# MCU.net
KiCad netlist of a schematic drawn in Altium Designer
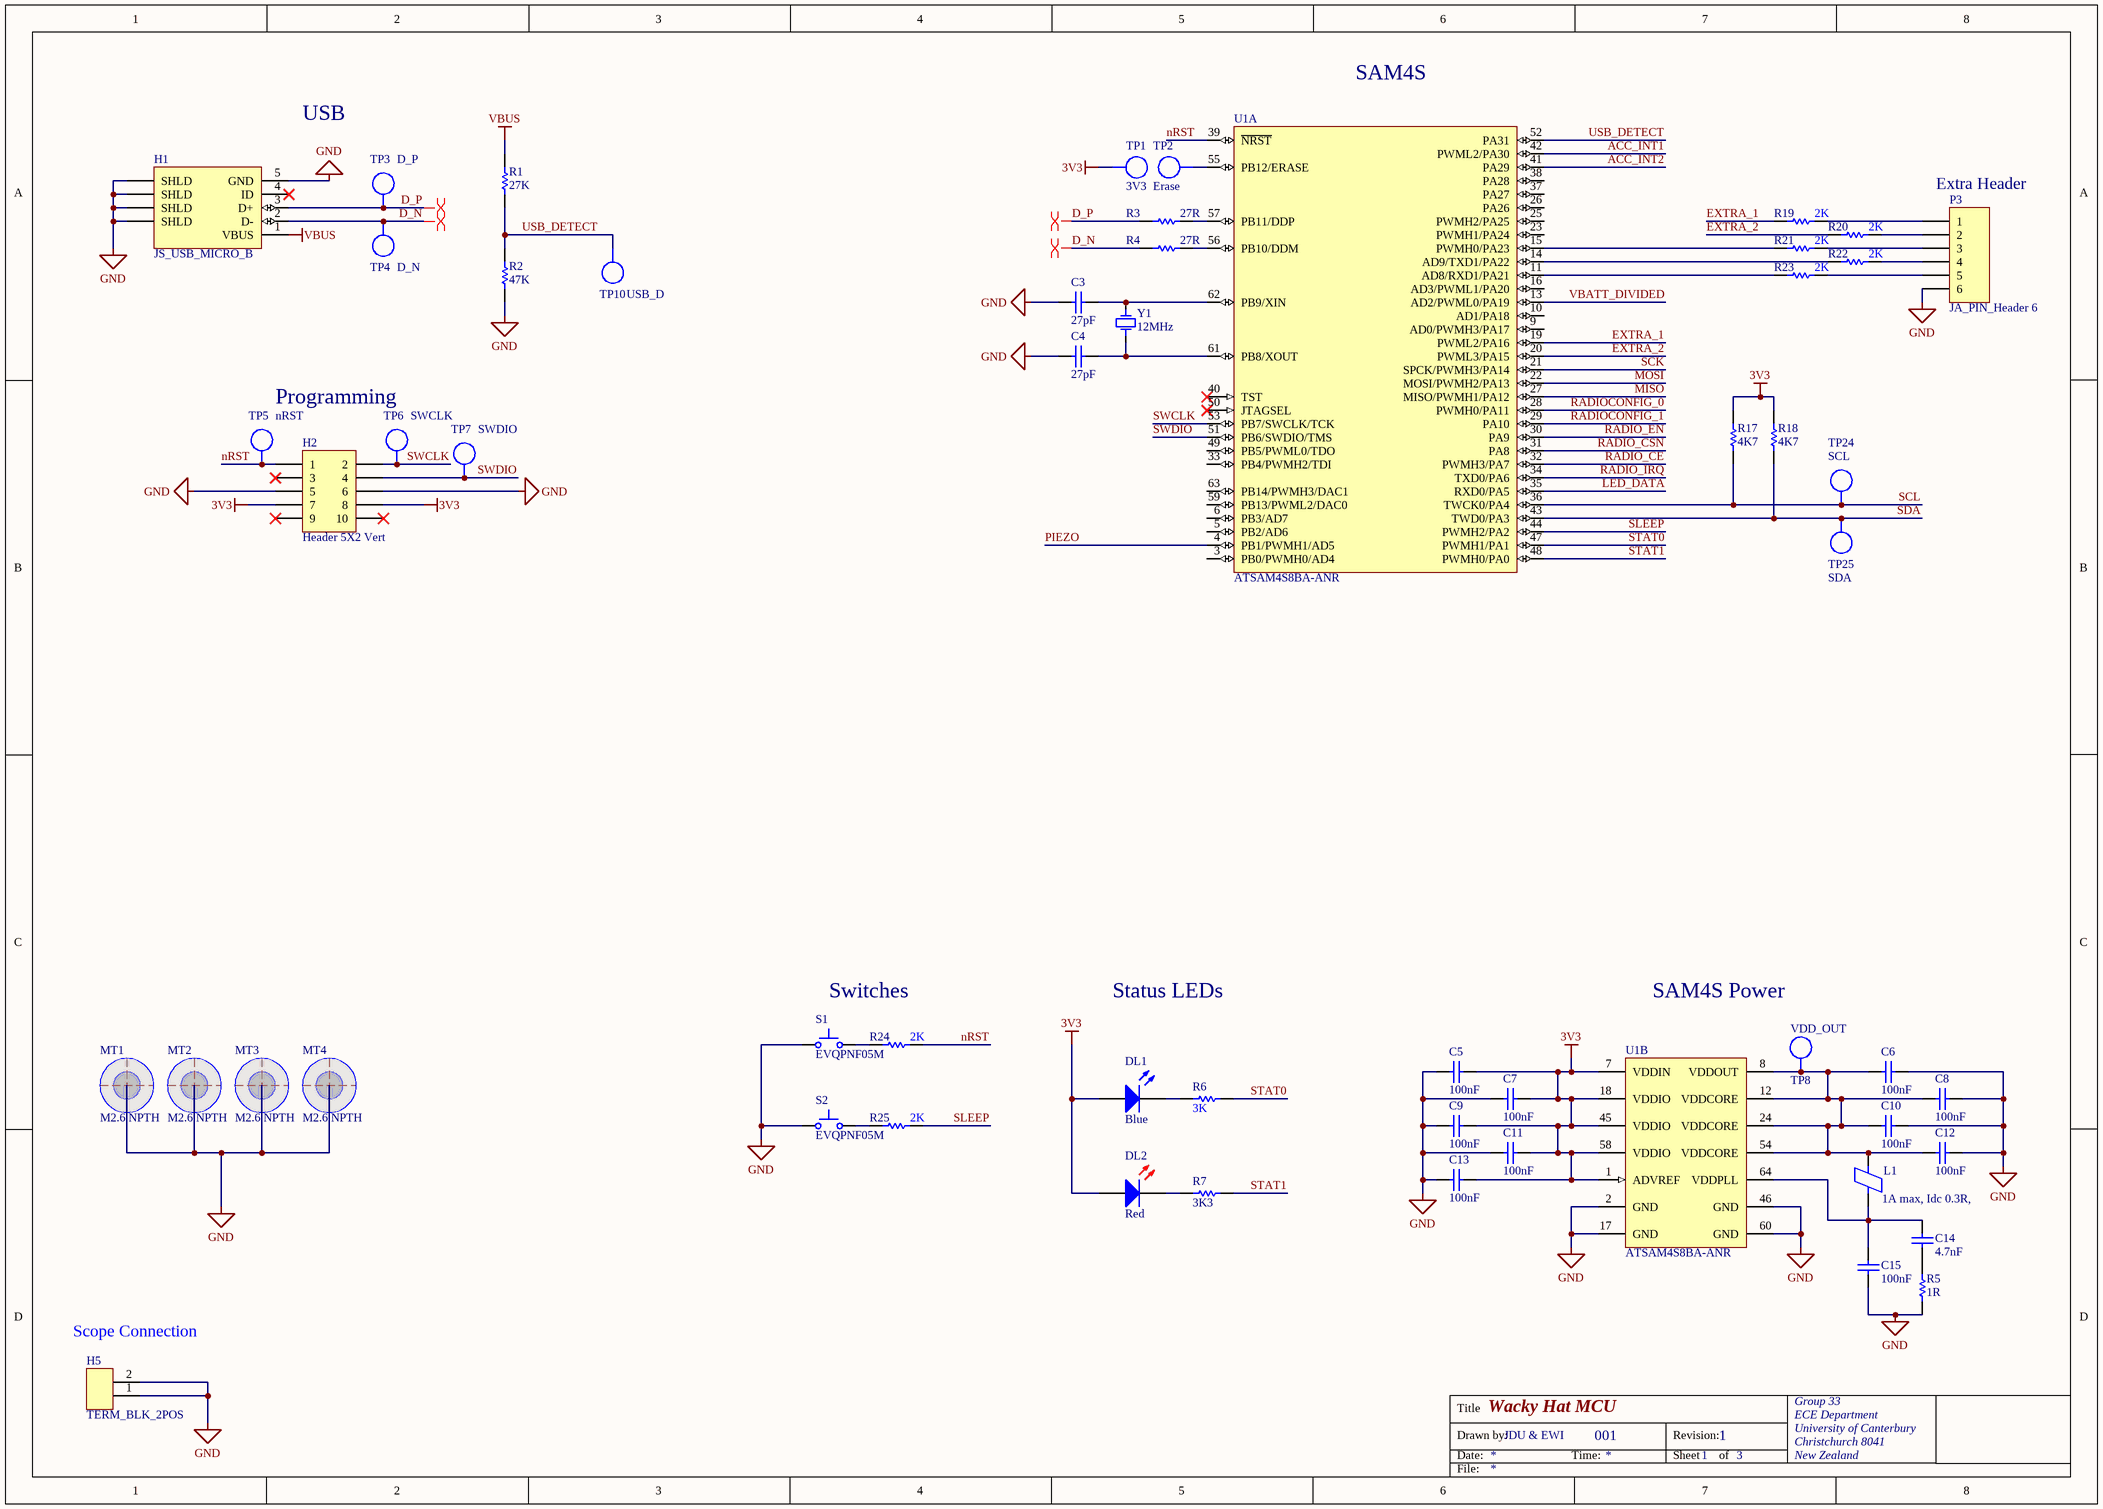
[diagram p0: MCU.SchDoc]

(export (version "E")
  (design (tool "Eeschema 10.0.6"))
  (components
    (comp (ref "C3")
      (value "27pF")
      (footprint "CAPC1608L")
      (description "CAP CER 27pF NPO/COG +-5% 50V 0603")
      (libsource (lib "ECE_ComponentsAD23") (part "CC_27pF_0603"))
    )
    (comp (ref "C4")
      (value "27pF")
      (footprint "CAPC1608L")
      (description "CAP CER 27pF NPO/COG +-5% 50V 0603")
      (libsource (lib "ECE_ComponentsAD23") (part "CC_27pF_0603"))
    )
    (comp (ref "C5")
      (value "100nF")
      (footprint "CAPC1608L")
      (description "CAP CER 100nF X7R +-10% 50V 0603")
      (libsource (lib "ECE_ComponentsAD23") (part "CC_100nF_0603"))
    )
    (comp (ref "C6")
      (value "100nF")
      (footprint "CAPC1608L")
      (description "CAP CER 100nF X7R +-10% 50V 0603")
      (libsource (lib "ECE_ComponentsAD23") (part "CC_100nF_0603"))
    )
    (comp (ref "C7")
      (value "100nF")
      (footprint "CAPC1608L")
      (description "CAP CER 100nF X7R +-10% 50V 0603")
      (libsource (lib "ECE_ComponentsAD23") (part "CC_100nF_0603"))
    )
    (comp (ref "C8")
      (value "100nF")
      (footprint "CAPC1608L")
      (description "CAP CER 100nF X7R +-10% 50V 0603")
      (libsource (lib "ECE_ComponentsAD23") (part "CC_100nF_0603"))
    )
    (comp (ref "C9")
      (value "100nF")
      (footprint "CAPC1608L")
      (description "CAP CER 100nF X7R +-10% 50V 0603")
      (libsource (lib "ECE_ComponentsAD23") (part "CC_100nF_0603"))
    )
    (comp (ref "C10")
      (value "100nF")
      (footprint "CAPC1608L")
      (description "CAP CER 100nF X7R +-10% 50V 0603")
      (libsource (lib "ECE_ComponentsAD23") (part "CC_100nF_0603"))
    )
    (comp (ref "C11")
      (value "100nF")
      (footprint "CAPC1608L")
      (description "CAP CER 100nF X7R +-10% 50V 0603")
      (libsource (lib "ECE_ComponentsAD23") (part "CC_100nF_0603"))
    )
    (comp (ref "C12")
      (value "100nF")
      (footprint "CAPC1608L")
      (description "CAP CER 100nF X7R +-10% 50V 0603")
      (libsource (lib "ECE_ComponentsAD23") (part "CC_100nF_0603"))
    )
    (comp (ref "C13")
      (value "100nF")
      (footprint "CAPC1608L")
      (description "CAP CER 100nF X7R +-10% 50V 0603")
      (libsource (lib "ECE_ComponentsAD23") (part "CC_100nF_0603"))
    )
    (comp (ref "C14")
      (value "4.7nF")
      (footprint "CAPC1608L")
      (description "CAP CER 4.7nF X7R +-10% 50V 0603")
      (libsource (lib "ECE_ComponentsAD23") (part "CC_4.7nF_0603"))
    )
    (comp (ref "C15")
      (value "100nF")
      (footprint "CAPC1608L")
      (description "CAP CER 100nF X7R +-10% 50V 0603")
      (libsource (lib "ECE_ComponentsAD23") (part "CC_100nF_0603"))
    )
    (comp (ref "DL1")
      (value "Blue")
      (footprint "WL-SMCW0603")
      (description "LED Blue 270mcd 0603 SMD")
      (fields
        (field (name "MANUFACTURER") "WURTH ELEKTRONIK")
        (field (name "MANUFACTURER PART NUMBER") "150060BS75000")
        (field (name "LED COLOUR") "Blue")
      )
      (libsource (lib "ECE_ComponentsAD23") (part "DL_150060BS75000"))
    )
    (comp (ref "DL2")
      (value "Red")
      (footprint "WL-SMCW0603")
      (description "LED Red 250mcd 0603 SMD")
      (fields
        (field (name "MANUFACTURER") "WURTH ELEKTRONIK")
        (field (name "MANUFACTURER PART NUMBER") "150060RS75000")
        (field (name "LED COLOUR") "Red")
      )
      (libsource (lib "ECE_ComponentsAD23") (part "DL_150060RS75000"))
    )
    (comp (ref "H1")
      (value "JS_USB_MICRO_B")
      (footprint "FCI_USB_10118194-0001LF")
      (description "CONN USB MICRO B RECPT SMT R/A")
      (fields (field (name "MANUFACTURER") "FCI") (field (name "MANUFACTURER PART NUMBER") "10118194-0001LF"))
      (libsource (lib "ECE_ComponentsAD23") (part "JS_USB_MICRO_B_SMT"))
    )
    (comp (ref "H2")
      (value "Header 5X2 Vert")
      (footprint "IDC2.54-V10D")
      (description "IDC Header, 2,54mm, 10-Pin, Vert")
      (libsource (lib "ECE_ComponentsAD23") (part "JA_HDR_IDC_5X2_VERT"))
    )
    (comp (ref "H5")
      (value "TERM_BLK_2POS")
      (footprint "TERM_BLK_2POS")
      (description "2 Position Terminal Block 7.62mm spacing")
      (libsource (lib "ENCE461AD23") (part "TERM_BLK_2POS"))
    )
    (comp (ref "L1")
      (value "1A max, Idc 0.3R,")
      (footprint "INDC3216L")
      (description "Ferrite Bead, Rdc 0.3R, Z100MHZ 600R, Imax 1A, SMD 1206")
      (fields
        (field (name "MANUFACTURER") "FAIR-RITE")
        (field (name "MANUFACTURER PART NUMBER") "2512066017Y1")
      )
      (libsource (lib "ECE_ComponentsAD23") (part "IN_Ferrite-Bead"))
    )
    (comp (ref "MT1")
      (value "M2.6 NPTH")
      (footprint "MNT-HOLE_2.6mm_NPTH")
      (description "Fixing M2.6 Mount Hole NPTH")
      (fields (field (name "MANUFACTURER") "Hi-Q"))
      (libsource (lib "ECE_ComponentsAD23") (part "MC_M2.6_HOLE"))
    )
    (comp (ref "MT2")
      (value "M2.6 NPTH")
      (footprint "MNT-HOLE_2.6mm_NPTH")
      (description "Fixing M2.6 Mount Hole NPTH")
      (fields (field (name "MANUFACTURER") "Hi-Q"))
      (libsource (lib "ECE_ComponentsAD23") (part "MC_M2.6_HOLE"))
    )
    (comp (ref "MT3")
      (value "M2.6 NPTH")
      (footprint "MNT-HOLE_2.6mm_NPTH")
      (description "Fixing M2.6 Mount Hole NPTH")
      (fields (field (name "MANUFACTURER") "Hi-Q"))
      (libsource (lib "ECE_ComponentsAD23") (part "MC_M2.6_HOLE"))
    )
    (comp (ref "MT4")
      (value "M2.6 NPTH")
      (footprint "MNT-HOLE_2.6mm_NPTH")
      (description "Fixing M2.6 Mount Hole NPTH")
      (fields (field (name "MANUFACTURER") "Hi-Q"))
      (libsource (lib "ECE_ComponentsAD23") (part "MC_M2.6_HOLE"))
    )
    (comp (ref "P3")
      (value "JA_PIN_Header 6")
      (footprint "HDR1X6")
      (description "Header, 6-Pin")
      (fields (field (name "PUBLISHER") "Altium Limited"))
      (libsource (lib "ECE_ComponentsAD23") (part "JA_PIN_Header 6"))
    )
    (comp (ref "R1")
      (value "27K")
      (footprint "RESC1608L")
      (description "RES 27K OHM 1/10W 5% 0603 SMD")
      (libsource (lib "ECE_ComponentsAD23") (part "RS_27K"))
    )
    (comp (ref "R2")
      (value "47K")
      (footprint "RESC1608N")
      (description "RES 47.0K OHM 1/10W 5% 0603 SMD")
      (libsource (lib "ECE_ComponentsAD23") (part "RS_47K"))
    )
    (comp (ref "R3")
      (value "27R")
      (footprint "RESC1608L")
      (description "RES 27 OHM 1/10W 5% 0603 SMD")
      (libsource (lib "ECE_ComponentsAD23") (part "RS_27R"))
    )
    (comp (ref "R4")
      (value "27R")
      (footprint "RESC1608L")
      (description "RES 27 OHM 1/10W 5% 0603 SMD")
      (libsource (lib "ECE_ComponentsAD23") (part "RS_27R"))
    )
    (comp (ref "R5")
      (value "1R")
      (footprint "RESC3216L")
      (description "RES 1R OHM 1/4W 5% 1206 SMD")
      (libsource (lib "ECE_ComponentsAD23") (part "RT_1R"))
    )
    (comp (ref "R6")
      (value "3K")
      (footprint "RESC1608L")
      (description "RES 3K OHM 1/10W 5% 0603 SMD")
      (libsource (lib "ECE_ComponentsAD23") (part "RS_3K"))
    )
    (comp (ref "R7")
      (value "3K3")
      (footprint "RESC1608L")
      (description "RES 1.5K OHM 1/10W 5% 0603 SMD")
      (libsource (lib "ECE_ComponentsAD23") (part "RS_1K5"))
    )
    (comp (ref "R17")
      (value "4K7")
      (footprint "RESC1608L")
      (description "RES 4.7K OHM 1/10W 5% 0603 SMD")
      (libsource (lib "ECE_ComponentsAD23") (part "RS_4K7"))
    )
    (comp (ref "R18")
      (value "4K7")
      (footprint "RESC1608L")
      (description "RES 4.7K OHM 1/10W 5% 0603 SMD")
      (libsource (lib "ECE_ComponentsAD23") (part "RS_4K7"))
    )
    (comp (ref "R19")
      (value "2K")
      (footprint "RESC1608L")
      (description "RES 2K OHM 1/10W 5% 0603 SMD")
      (libsource (lib "ECE_ComponentsAD23") (part "RS_2K"))
    )
    (comp (ref "R20")
      (value "2K")
      (footprint "RESC1608L")
      (description "RES 2K OHM 1/10W 5% 0603 SMD")
      (libsource (lib "ECE_ComponentsAD23") (part "RS_2K"))
    )
    (comp (ref "R21")
      (value "2K")
      (footprint "RESC1608L")
      (description "RES 2K OHM 1/10W 5% 0603 SMD")
      (libsource (lib "ECE_ComponentsAD23") (part "RS_2K"))
    )
    (comp (ref "R22")
      (value "2K")
      (footprint "RESC1608L")
      (description "RES 2K OHM 1/10W 5% 0603 SMD")
      (libsource (lib "ECE_ComponentsAD23") (part "RS_2K"))
    )
    (comp (ref "R23")
      (value "2K")
      (footprint "RESC1608L")
      (description "RES 2K OHM 1/10W 5% 0603 SMD")
      (libsource (lib "ECE_ComponentsAD23") (part "RS_2K"))
    )
    (comp (ref "R24")
      (value "2K")
      (footprint "RESC1608L")
      (description "RES 2K OHM 1/10W 5% 0603 SMD")
      (libsource (lib "ECE_ComponentsAD23") (part "RS_2K"))
    )
    (comp (ref "R25")
      (value "2K")
      (footprint "RESC1608L")
      (description "RES 2K OHM 1/10W 5% 0603 SMD")
      (libsource (lib "ECE_ComponentsAD23") (part "RS_2K"))
    )
    (comp (ref "S1")
      (value "EVQPNF05M")
      (footprint "EVQPNF05M")
      (description "Panasonic 6 x 3.5mm SMD Light Touch Switch Type SMD")
      (fields (field (name "MANUFACTURER") "Panasonic"))
      (libsource (lib "ECE_ComponentsAD23") (part "WS_EVQPNF05M"))
    )
    (comp (ref "S2")
      (value "EVQPNF05M")
      (footprint "EVQPNF05M")
      (description "Panasonic 6 x 3.5mm SMD Light Touch Switch Type SMD")
      (fields (field (name "MANUFACTURER") "Panasonic"))
      (libsource (lib "ECE_ComponentsAD23") (part "WS_EVQPNF05M"))
    )
    (comp (ref "TP1")
      (value "3V3")
      (footprint "TP_1206")
      (description "Test-Point 3.3x1.6x2.1mm SMD")
      (fields
        (field (name "MANUFACTURER") "Harwin Inc")
        (field (name "MANUFACTURER PART NUMBER") "S1751-46R")
      )
      (libsource (lib "ECE_ComponentsAD23") (part "TP_1206"))
    )
    (comp (ref "TP2")
      (value "Erase")
      (footprint "TP_1206")
      (description "Test-Point 3.3x1.6x2.1mm SMD")
      (fields
        (field (name "MANUFACTURER") "Harwin Inc")
        (field (name "MANUFACTURER PART NUMBER") "S1751-46R")
      )
      (libsource (lib "ECE_ComponentsAD23") (part "TP_1206"))
    )
    (comp (ref "TP3")
      (value "D_P")
      (footprint "TP_1206")
      (description "Test-Point 3.3x1.6x2.1mm SMD")
      (fields
        (field (name "MANUFACTURER") "Harwin Inc")
        (field (name "MANUFACTURER PART NUMBER") "S1751-46R")
      )
      (libsource (lib "ECE_ComponentsAD23") (part "TP_1206"))
    )
    (comp (ref "TP4")
      (value "D_N")
      (footprint "TP_1206")
      (description "Test-Point 3.3x1.6x2.1mm SMD")
      (fields
        (field (name "MANUFACTURER") "Harwin Inc")
        (field (name "MANUFACTURER PART NUMBER") "S1751-46R")
      )
      (libsource (lib "ECE_ComponentsAD23") (part "TP_1206"))
    )
    (comp (ref "TP5")
      (value "nRST")
      (footprint "TP_1206")
      (description "Test-Point 3.3x1.6x2.1mm SMD")
      (fields
        (field (name "MANUFACTURER") "Harwin Inc")
        (field (name "MANUFACTURER PART NUMBER") "S1751-46R")
      )
      (libsource (lib "ECE_ComponentsAD23") (part "TP_1206"))
    )
    (comp (ref "TP6")
      (value "SWCLK")
      (footprint "TP_1206")
      (description "Test-Point 3.3x1.6x2.1mm SMD")
      (fields
        (field (name "MANUFACTURER") "Harwin Inc")
        (field (name "MANUFACTURER PART NUMBER") "S1751-46R")
      )
      (libsource (lib "ECE_ComponentsAD23") (part "TP_1206"))
    )
    (comp (ref "TP7")
      (value "SWDIO")
      (footprint "TP_1206")
      (description "Test-Point 3.3x1.6x2.1mm SMD")
      (fields
        (field (name "MANUFACTURER") "Harwin Inc")
        (field (name "MANUFACTURER PART NUMBER") "S1751-46R")
      )
      (libsource (lib "ECE_ComponentsAD23") (part "TP_1206"))
    )
    (comp (ref "TP8")
      (value "VDD_OUT")
      (footprint "TP_1206")
      (description "Test-Point 3.3x1.6x2.1mm SMD")
      (fields
        (field (name "MANUFACTURER") "Harwin Inc")
        (field (name "MANUFACTURER PART NUMBER") "S1751-46R")
      )
      (libsource (lib "ECE_ComponentsAD23") (part "TP_1206"))
    )
    (comp (ref "TP10")
      (value "USB_D")
      (footprint "TP_1206")
      (description "Test-Point 3.3x1.6x2.1mm SMD")
      (fields
        (field (name "MANUFACTURER") "Harwin Inc")
        (field (name "MANUFACTURER PART NUMBER") "S1751-46R")
      )
      (libsource (lib "ECE_ComponentsAD23") (part "TP_1206"))
    )
    (comp (ref "TP24")
      (value "SCL")
      (footprint "TP_1206")
      (description "Test-Point 3.3x1.6x2.1mm SMD")
      (fields
        (field (name "MANUFACTURER") "Harwin Inc")
        (field (name "MANUFACTURER PART NUMBER") "S1751-46R")
      )
      (libsource (lib "ECE_ComponentsAD23") (part "TP_1206"))
    )
    (comp (ref "TP25")
      (value "SDA")
      (footprint "TP_1206")
      (description "Test-Point 3.3x1.6x2.1mm SMD")
      (fields
        (field (name "MANUFACTURER") "Harwin Inc")
        (field (name "MANUFACTURER PART NUMBER") "S1751-46R")
      )
      (libsource (lib "ECE_ComponentsAD23") (part "TP_1206"))
    )
    (comp (ref "U1")
      (value "ATSAM4S8BA-ANR")
      (footprint "LQFP64_L")
      (description "IC MCU 32BIT 512KB FLASH 64LQFP")
      (fields (field (name "MANUFACTURER") "Atmel"))
      (libsource (lib "ECE_ComponentsAD23") (part "SE_ATSAM4S16BA-MU"))
    )
    (comp (ref "Y1")
      (value "12MHz")
      (footprint "6.0X3.5-4")
      (description "CRYSTAL 12MHZ 18PF 6X3.5mm SMD")
      (fields
        (field (name "MANUFACTURER") "CTS-Frequency Controls")
        (field (name "MANUFACTURER PART NUMBER") "406C35D12M00000")
        (field (name "FREQUENCY") "12MHz")
      )
      (libsource (lib "ECE_ComponentsAD23") (part "XT_CRYSTAL_12MHz_18pF"))
    )
  )
  (nets
    (net (code "1") (name "/ACC_INT1") (class "Default")
      (node (ref "U1") (pin "42") (pinfunction "PWML2/PA30_42") (pintype "bidirectional"))
    )
    (net (code "2") (name "/ACC_INT2") (class "Default")
      (node (ref "U1") (pin "41") (pinfunction "PA29_41") (pintype "bidirectional"))
    )
    (net (code "3") (name "/D_N") (class "Default")
      (node (ref "H1") (pin "2") (pinfunction "D-_2") (pintype "bidirectional"))
      (node (ref "R4") (pin "1") (pinfunction "1_1") (pintype "passive"))
      (node (ref "TP4") (pin "1") (pinfunction "1_1") (pintype "passive"))
    )
    (net (code "4") (name "/D_P") (class "Default")
      (node (ref "H1") (pin "3") (pinfunction "D+_3") (pintype "bidirectional"))
      (node (ref "R3") (pin "1") (pinfunction "1_1") (pintype "passive"))
      (node (ref "TP3") (pin "1") (pinfunction "1_1") (pintype "passive"))
    )
    (net (code "5") (name "/EXTRA_1") (class "Default")
      (node (ref "R19") (pin "1") (pinfunction "1_1") (pintype "passive"))
      (node (ref "U1") (pin "19") (pinfunction "PWML2/PA16_19") (pintype "bidirectional"))
    )
    (net (code "6") (name "/EXTRA_2") (class "Default")
      (node (ref "R20") (pin "1") (pinfunction "1_1") (pintype "passive"))
      (node (ref "U1") (pin "20") (pinfunction "PWML3/PA15_20") (pintype "bidirectional"))
    )
    (net (code "7") (name "/LED_DATA") (class "Default")
      (node (ref "U1") (pin "35") (pinfunction "RXD0/PA5_35") (pintype "bidirectional"))
    )
    (net (code "8") (name "/MISO") (class "Default")
      (node (ref "U1") (pin "27") (pinfunction "MISO/PWMH1/PA12_27") (pintype "bidirectional"))
    )
    (net (code "9") (name "/MOSI") (class "Default")
      (node (ref "U1") (pin "22") (pinfunction "MOSI/PWMH2/PA13_22") (pintype "bidirectional"))
    )
    (net (code "10") (name "/PIEZO") (class "Default")
      (node (ref "U1") (pin "4") (pinfunction "PB1/PWMH1/AD5_4") (pintype "bidirectional"))
    )
    (net (code "11") (name "/RADIOCONFIG_0") (class "Default")
      (node (ref "U1") (pin "28") (pinfunction "PWMH0/PA11_28") (pintype "bidirectional"))
    )
    (net (code "12") (name "/RADIOCONFIG_1") (class "Default")
      (node (ref "U1") (pin "29") (pinfunction "PA10_29") (pintype "bidirectional"))
    )
    (net (code "13") (name "/RADIO_CE") (class "Default")
      (node (ref "U1") (pin "32") (pinfunction "PWMH3/PA7_32") (pintype "bidirectional"))
    )
    (net (code "14") (name "/RADIO_CSN") (class "Default")
      (node (ref "U1") (pin "31") (pinfunction "PA8_31") (pintype "bidirectional"))
    )
    (net (code "15") (name "/RADIO_EN") (class "Default")
      (node (ref "U1") (pin "30") (pinfunction "PA9_30") (pintype "bidirectional"))
    )
    (net (code "16") (name "/RADIO_IRQ") (class "Default")
      (node (ref "U1") (pin "34") (pinfunction "TXD0/PA6_34") (pintype "bidirectional"))
    )
    (net (code "17") (name "/SCK") (class "Default")
      (node (ref "U1") (pin "21") (pinfunction "SPCK/PWMH3/PA14_21") (pintype "bidirectional"))
    )
    (net (code "18") (name "/SCL") (class "Default")
      (node (ref "R17") (pin "1") (pinfunction "1_1") (pintype "passive"))
      (node (ref "TP24") (pin "1") (pinfunction "1_1") (pintype "passive"))
      (node (ref "U1") (pin "36") (pinfunction "TWCK0/PA4_36") (pintype "bidirectional"))
    )
    (net (code "19") (name "/SDA") (class "Default")
      (node (ref "R18") (pin "1") (pinfunction "1_1") (pintype "passive"))
      (node (ref "TP25") (pin "1") (pinfunction "1_1") (pintype "passive"))
      (node (ref "U1") (pin "43") (pinfunction "TWD0/PA3_43") (pintype "bidirectional"))
    )
    (net (code "20") (name "/SLEEP") (class "Default")
      (node (ref "R25") (pin "2") (pinfunction "2_2") (pintype "passive"))
      (node (ref "U1") (pin "44") (pinfunction "PWMH2/PA2_44") (pintype "bidirectional"))
    )
    (net (code "21") (name "/STAT0") (class "Default")
      (node (ref "R6") (pin "2") (pinfunction "2_2") (pintype "passive"))
      (node (ref "U1") (pin "47") (pinfunction "PWMH1/PA1_47") (pintype "bidirectional"))
    )
    (net (code "22") (name "/STAT1") (class "Default")
      (node (ref "R7") (pin "2") (pinfunction "2_2") (pintype "passive"))
      (node (ref "U1") (pin "48") (pinfunction "PWMH0/PA0_48") (pintype "bidirectional"))
    )
    (net (code "23") (name "/SWCLK") (class "Default")
      (node (ref "H2") (pin "2") (pinfunction "2_2") (pintype "passive"))
      (node (ref "TP6") (pin "1") (pinfunction "1_1") (pintype "passive"))
      (node (ref "U1") (pin "53") (pinfunction "PB7/SWCLK/TCK_53") (pintype "bidirectional"))
    )
    (net (code "24") (name "/SWDIO") (class "Default")
      (node (ref "H2") (pin "4") (pinfunction "4_4") (pintype "passive"))
      (node (ref "TP7") (pin "1") (pinfunction "1_1") (pintype "passive"))
      (node (ref "U1") (pin "51") (pinfunction "PB6/SWDIO/TMS_51") (pintype "bidirectional"))
    )
    (net (code "25") (name "/USB_DETECT") (class "Default")
      (node (ref "R1") (pin "1") (pinfunction "1_1") (pintype "passive"))
      (node (ref "R2") (pin "2") (pinfunction "2_2") (pintype "passive"))
      (node (ref "TP10") (pin "1") (pinfunction "1_1") (pintype "passive"))
      (node (ref "U1") (pin "52") (pinfunction "PA31_52") (pintype "bidirectional"))
    )
    (net (code "26") (name "/VBATT_DIVIDED") (class "Default")
      (node (ref "U1") (pin "13") (pinfunction "AD2/PWML0/PA19_13") (pintype "bidirectional"))
    )
    (net (code "27") (name "/nRST") (class "Default")
      (node (ref "H2") (pin "1") (pinfunction "1_1") (pintype "passive"))
      (node (ref "R24") (pin "2") (pinfunction "2_2") (pintype "passive"))
      (node (ref "TP5") (pin "1") (pinfunction "1_1") (pintype "passive"))
      (node (ref "U1") (pin "39") (pinfunction "~{NRST}_39") (pintype "bidirectional"))
    )
    (net (code "28") (name "3V3") (class "Default")
      (node (ref "C11") (pin "2") (pinfunction "2_2") (pintype "passive"))
      (node (ref "C13") (pin "2") (pinfunction "2_2") (pintype "passive"))
      (node (ref "C5") (pin "2") (pinfunction "2_2") (pintype "passive"))
      (node (ref "C7") (pin "2") (pinfunction "2_2") (pintype "passive"))
      (node (ref "C9") (pin "2") (pinfunction "2_2") (pintype "passive"))
      (node (ref "DL1") (pin "2") (pinfunction "A_2") (pintype "passive"))
      (node (ref "DL2") (pin "2") (pinfunction "A_2") (pintype "passive"))
      (node (ref "H2") (pin "7") (pinfunction "7_7") (pintype "passive"))
      (node (ref "H2") (pin "8") (pinfunction "8_8") (pintype "passive"))
      (node (ref "R17") (pin "2") (pinfunction "2_2") (pintype "passive"))
      (node (ref "R18") (pin "2") (pinfunction "2_2") (pintype "passive"))
      (node (ref "TP1") (pin "1") (pinfunction "1_1") (pintype "passive"))
      (node (ref "U1") (pin "1") (pinfunction "ADVREF_1") (pintype "input"))
      (node (ref "U1") (pin "18") (pinfunction "VDDIO_18") (pintype "power_in"))
      (node (ref "U1") (pin "45") (pinfunction "VDDIO_45") (pintype "power_in"))
      (node (ref "U1") (pin "58") (pinfunction "VDDIO_58") (pintype "power_in"))
      (node (ref "U1") (pin "7") (pinfunction "VDDIN_7") (pintype "power_in"))
    )
    (net (code "29") (name "GND") (class "Default")
      (node (ref "C10") (pin "2") (pinfunction "2_2") (pintype "passive"))
      (node (ref "C11") (pin "1") (pinfunction "1_1") (pintype "passive"))
      (node (ref "C12") (pin "2") (pinfunction "2_2") (pintype "passive"))
      (node (ref "C13") (pin "1") (pinfunction "1_1") (pintype "passive"))
      (node (ref "C15") (pin "1") (pinfunction "1_1") (pintype "passive"))
      (node (ref "C3") (pin "1") (pinfunction "1_1") (pintype "passive"))
      (node (ref "C4") (pin "1") (pinfunction "1_1") (pintype "passive"))
      (node (ref "C5") (pin "1") (pinfunction "1_1") (pintype "passive"))
      (node (ref "C6") (pin "2") (pinfunction "2_2") (pintype "passive"))
      (node (ref "C7") (pin "1") (pinfunction "1_1") (pintype "passive"))
      (node (ref "C8") (pin "2") (pinfunction "2_2") (pintype "passive"))
      (node (ref "C9") (pin "1") (pinfunction "1_1") (pintype "passive"))
      (node (ref "H1") (pin "5") (pinfunction "GND_5") (pintype "passive"))
      (node (ref "H1") (pin "6") (pinfunction "SHLD_6") (pintype "passive"))
      (node (ref "H2") (pin "5") (pinfunction "5_5") (pintype "passive"))
      (node (ref "H2") (pin "6") (pinfunction "6_6") (pintype "passive"))
      (node (ref "H5") (pin "1") (pintype "passive"))
      (node (ref "H5") (pin "2") (pintype "passive"))
      (node (ref "P3") (pin "6") (pinfunction "6_6") (pintype "passive"))
      (node (ref "R2") (pin "1") (pinfunction "1_1") (pintype "passive"))
      (node (ref "R5") (pin "1") (pinfunction "1_1") (pintype "passive"))
      (node (ref "S1") (pin "1") (pintype "passive"))
      (node (ref "S2") (pin "1") (pintype "passive"))
      (node (ref "U1") (pin "17") (pinfunction "GND_17") (pintype "power_in"))
      (node (ref "U1") (pin "2") (pinfunction "GND_2") (pintype "power_in"))
      (node (ref "U1") (pin "46") (pinfunction "GND_46") (pintype "power_in"))
      (node (ref "U1") (pin "60") (pinfunction "GND_60") (pintype "power_in"))
    )
    (net (code "30") (name "Net-(C14-Pad1)") (class "Default")
      (node (ref "C14") (pin "1") (pinfunction "1_1") (pintype "passive"))
      (node (ref "R5") (pin "2") (pinfunction "2_2") (pintype "passive"))
    )
    (net (code "31") (name "Net-(DL1-K)") (class "Default")
      (node (ref "DL1") (pin "1") (pinfunction "K_1") (pintype "passive"))
      (node (ref "R6") (pin "1") (pinfunction "1_1") (pintype "passive"))
    )
    (net (code "32") (name "Net-(DL2-K)") (class "Default")
      (node (ref "DL2") (pin "1") (pinfunction "K_1") (pintype "passive"))
      (node (ref "R7") (pin "1") (pinfunction "1_1") (pintype "passive"))
    )
    (net (code "33") (name "Net-(P3-Pad1)") (class "Default")
      (node (ref "P3") (pin "1") (pinfunction "1_1") (pintype "passive"))
      (node (ref "R19") (pin "2") (pinfunction "2_2") (pintype "passive"))
    )
    (net (code "34") (name "Net-(P3-Pad2)") (class "Default")
      (node (ref "P3") (pin "2") (pinfunction "2_2") (pintype "passive"))
      (node (ref "R20") (pin "2") (pinfunction "2_2") (pintype "passive"))
    )
    (net (code "35") (name "Net-(P3-Pad3)") (class "Default")
      (node (ref "P3") (pin "3") (pinfunction "3_3") (pintype "passive"))
      (node (ref "R21") (pin "2") (pinfunction "2_2") (pintype "passive"))
    )
    (net (code "36") (name "Net-(P3-Pad4)") (class "Default")
      (node (ref "P3") (pin "4") (pinfunction "4_4") (pintype "passive"))
      (node (ref "R22") (pin "2") (pinfunction "2_2") (pintype "passive"))
    )
    (net (code "37") (name "Net-(P3-Pad5)") (class "Default")
      (node (ref "P3") (pin "5") (pinfunction "5_5") (pintype "passive"))
      (node (ref "R23") (pin "2") (pinfunction "2_2") (pintype "passive"))
    )
    (net (code "38") (name "Net-(R24-Pad1)") (class "Default")
      (node (ref "R24") (pin "1") (pinfunction "1_1") (pintype "passive"))
      (node (ref "S1") (pin "2") (pintype "passive"))
    )
    (net (code "39") (name "Net-(R25-Pad1)") (class "Default")
      (node (ref "R25") (pin "1") (pinfunction "1_1") (pintype "passive"))
      (node (ref "S2") (pin "2") (pintype "passive"))
    )
    (net (code "40") (name "Net-(U1A-AD8{slash}RXD1{slash}PA21)") (class "Default")
      (node (ref "R23") (pin "1") (pinfunction "1_1") (pintype "passive"))
      (node (ref "U1") (pin "11") (pinfunction "AD8/RXD1/PA21_11") (pintype "bidirectional"))
    )
    (net (code "41") (name "Net-(U1A-AD9{slash}TXD1{slash}PA22)") (class "Default")
      (node (ref "R22") (pin "1") (pinfunction "1_1") (pintype "passive"))
      (node (ref "U1") (pin "14") (pinfunction "AD9/TXD1/PA22_14") (pintype "bidirectional"))
    )
    (net (code "42") (name "Net-(U1A-PB8{slash}XOUT)") (class "Default")
      (node (ref "C4") (pin "2") (pinfunction "2_2") (pintype "passive"))
      (node (ref "U1") (pin "61") (pinfunction "PB8/XOUT_61") (pintype "bidirectional"))
      (node (ref "Y1") (pin "1") (pinfunction "OSC1_1") (pintype "passive"))
    )
    (net (code "43") (name "Net-(U1A-PB9{slash}XIN)") (class "Default")
      (node (ref "C3") (pin "2") (pinfunction "2_2") (pintype "passive"))
      (node (ref "U1") (pin "62") (pinfunction "PB9/XIN_62") (pintype "bidirectional"))
      (node (ref "Y1") (pin "3") (pinfunction "OSC2_3") (pintype "passive"))
    )
    (net (code "44") (name "Net-(U1A-PB10{slash}DDM)") (class "Default")
      (node (ref "R4") (pin "2") (pinfunction "2_2") (pintype "passive"))
      (node (ref "U1") (pin "56") (pinfunction "PB10/DDM_56") (pintype "bidirectional"))
    )
    (net (code "45") (name "Net-(U1A-PB11{slash}DDP)") (class "Default")
      (node (ref "R3") (pin "2") (pinfunction "2_2") (pintype "passive"))
      (node (ref "U1") (pin "57") (pinfunction "PB11/DDP_57") (pintype "bidirectional"))
    )
    (net (code "46") (name "Net-(U1A-PB12{slash}ERASE)") (class "Default")
      (node (ref "TP2") (pin "1") (pinfunction "1_1") (pintype "passive"))
      (node (ref "U1") (pin "55") (pinfunction "PB12/ERASE_55") (pintype "bidirectional"))
    )
    (net (code "47") (name "Net-(U1A-PWMH0{slash}PA23)") (class "Default")
      (node (ref "R21") (pin "1") (pinfunction "1_1") (pintype "passive"))
      (node (ref "U1") (pin "15") (pinfunction "PWMH0/PA23_15") (pintype "bidirectional"))
    )
    (net (code "48") (name "Net-(U1B-VDDOUT)") (class "Default")
      (node (ref "C10") (pin "1") (pinfunction "1_1") (pintype "passive"))
      (node (ref "C12") (pin "1") (pinfunction "1_1") (pintype "passive"))
      (node (ref "C6") (pin "1") (pinfunction "1_1") (pintype "passive"))
      (node (ref "C8") (pin "1") (pinfunction "1_1") (pintype "passive"))
      (node (ref "L1") (pin "2") (pinfunction "2_2") (pintype "passive"))
      (node (ref "TP8") (pin "1") (pinfunction "1_1") (pintype "passive"))
      (node (ref "U1") (pin "12") (pinfunction "VDDCORE_12") (pintype "power_in"))
      (node (ref "U1") (pin "24") (pinfunction "VDDCORE_24") (pintype "power_in"))
      (node (ref "U1") (pin "54") (pinfunction "VDDCORE_54") (pintype "power_in"))
      (node (ref "U1") (pin "8") (pinfunction "VDDOUT_8") (pintype "power_in"))
    )
    (net (code "49") (name "Net-(U1B-VDDPLL)") (class "Default")
      (node (ref "C14") (pin "2") (pinfunction "2_2") (pintype "passive"))
      (node (ref "C15") (pin "2") (pinfunction "2_2") (pintype "passive"))
      (node (ref "L1") (pin "1") (pinfunction "1_1") (pintype "passive"))
      (node (ref "U1") (pin "64") (pinfunction "VDDPLL_64") (pintype "power_in"))
    )
    (net (code "50") (name "VBUS") (class "Default")
      (node (ref "H1") (pin "1") (pinfunction "VBUS_1") (pintype "power_in"))
      (node (ref "R1") (pin "2") (pinfunction "2_2") (pintype "passive"))
    )
    (net (code "51") (name "unconnected-(H1-ID-Pad4)") (class "Default")
      (node (ref "H1") (pin "4") (pinfunction "ID_4") (pintype "power_in+no_connect"))
    )
    (net (code "52") (name "unconnected-(H2-Pad3)") (class "Default")
      (node (ref "H2") (pin "3") (pinfunction "3_3") (pintype "passive+no_connect"))
    )
    (net (code "53") (name "unconnected-(H2-Pad9)") (class "Default")
      (node (ref "H2") (pin "9") (pinfunction "9_9") (pintype "passive+no_connect"))
    )
    (net (code "54") (name "unconnected-(H2-Pad10)") (class "Default")
      (node (ref "H2") (pin "10") (pinfunction "10_10") (pintype "passive+no_connect"))
    )
    (net (code "55") (name "unconnected-(U1A-AD0{slash}PWMH3{slash}PA17-Pad9)") (class "Default")
      (node (ref "U1") (pin "9") (pinfunction "AD0/PWMH3/PA17_9") (pintype "bidirectional"))
    )
    (net (code "56") (name "unconnected-(U1A-AD1{slash}PA18-Pad10)") (class "Default")
      (node (ref "U1") (pin "10") (pinfunction "AD1/PA18_10") (pintype "bidirectional"))
    )
    (net (code "57") (name "unconnected-(U1A-AD3{slash}PWML1{slash}PA20-Pad16)") (class "Default")
      (node (ref "U1") (pin "16") (pinfunction "AD3/PWML1/PA20_16") (pintype "bidirectional"))
    )
    (net (code "58") (name "unconnected-(U1A-JTAGSEL-Pad50)") (class "Default")
      (node (ref "U1") (pin "50") (pinfunction "JTAGSEL_50") (pintype "input+no_connect"))
    )
    (net (code "59") (name "unconnected-(U1A-PA26-Pad26)") (class "Default")
      (node (ref "U1") (pin "26") (pinfunction "PA26_26") (pintype "bidirectional"))
    )
    (net (code "60") (name "unconnected-(U1A-PA27-Pad37)") (class "Default")
      (node (ref "U1") (pin "37") (pinfunction "PA27_37") (pintype "bidirectional"))
    )
    (net (code "61") (name "unconnected-(U1A-PA28-Pad38)") (class "Default")
      (node (ref "U1") (pin "38") (pinfunction "PA28_38") (pintype "bidirectional"))
    )
    (net (code "62") (name "unconnected-(U1A-PB0{slash}PWMH0{slash}AD4-Pad3)") (class "Default")
      (node (ref "U1") (pin "3") (pinfunction "PB0/PWMH0/AD4_3") (pintype "bidirectional"))
    )
    (net (code "63") (name "unconnected-(U1A-PB2{slash}AD6-Pad5)") (class "Default")
      (node (ref "U1") (pin "5") (pinfunction "PB2/AD6_5") (pintype "bidirectional"))
    )
    (net (code "64") (name "unconnected-(U1A-PB3{slash}AD7-Pad6)") (class "Default")
      (node (ref "U1") (pin "6") (pinfunction "PB3/AD7_6") (pintype "bidirectional"))
    )
    (net (code "65") (name "unconnected-(U1A-PB4{slash}PWMH2{slash}TDI-Pad33)") (class "Default")
      (node (ref "U1") (pin "33") (pinfunction "PB4/PWMH2/TDI_33") (pintype "bidirectional"))
    )
    (net (code "66") (name "unconnected-(U1A-PB5{slash}PWML0{slash}TDO-Pad49)") (class "Default")
      (node (ref "U1") (pin "49") (pinfunction "PB5/PWML0/TDO_49") (pintype "bidirectional"))
    )
    (net (code "67") (name "unconnected-(U1A-PB13{slash}PWML2{slash}DAC0-Pad59)") (class "Default")
      (node (ref "U1") (pin "59") (pinfunction "PB13/PWML2/DAC0_59") (pintype "bidirectional"))
    )
    (net (code "68") (name "unconnected-(U1A-PB14{slash}PWMH3{slash}DAC1-Pad63)") (class "Default")
      (node (ref "U1") (pin "63") (pinfunction "PB14/PWMH3/DAC1_63") (pintype "bidirectional"))
    )
    (net (code "69") (name "unconnected-(U1A-PWMH1{slash}PA24-Pad23)") (class "Default")
      (node (ref "U1") (pin "23") (pinfunction "PWMH1/PA24_23") (pintype "bidirectional"))
    )
    (net (code "70") (name "unconnected-(U1A-PWMH2{slash}PA25-Pad25)") (class "Default")
      (node (ref "U1") (pin "25") (pinfunction "PWMH2/PA25_25") (pintype "bidirectional"))
    )
    (net (code "71") (name "unconnected-(U1A-TST-Pad40)") (class "Default")
      (node (ref "U1") (pin "40") (pinfunction "TST_40") (pintype "input+no_connect"))
    )
  )
)
